# 04.net
KiCad netlist of a schematic drawn in EasyEDA
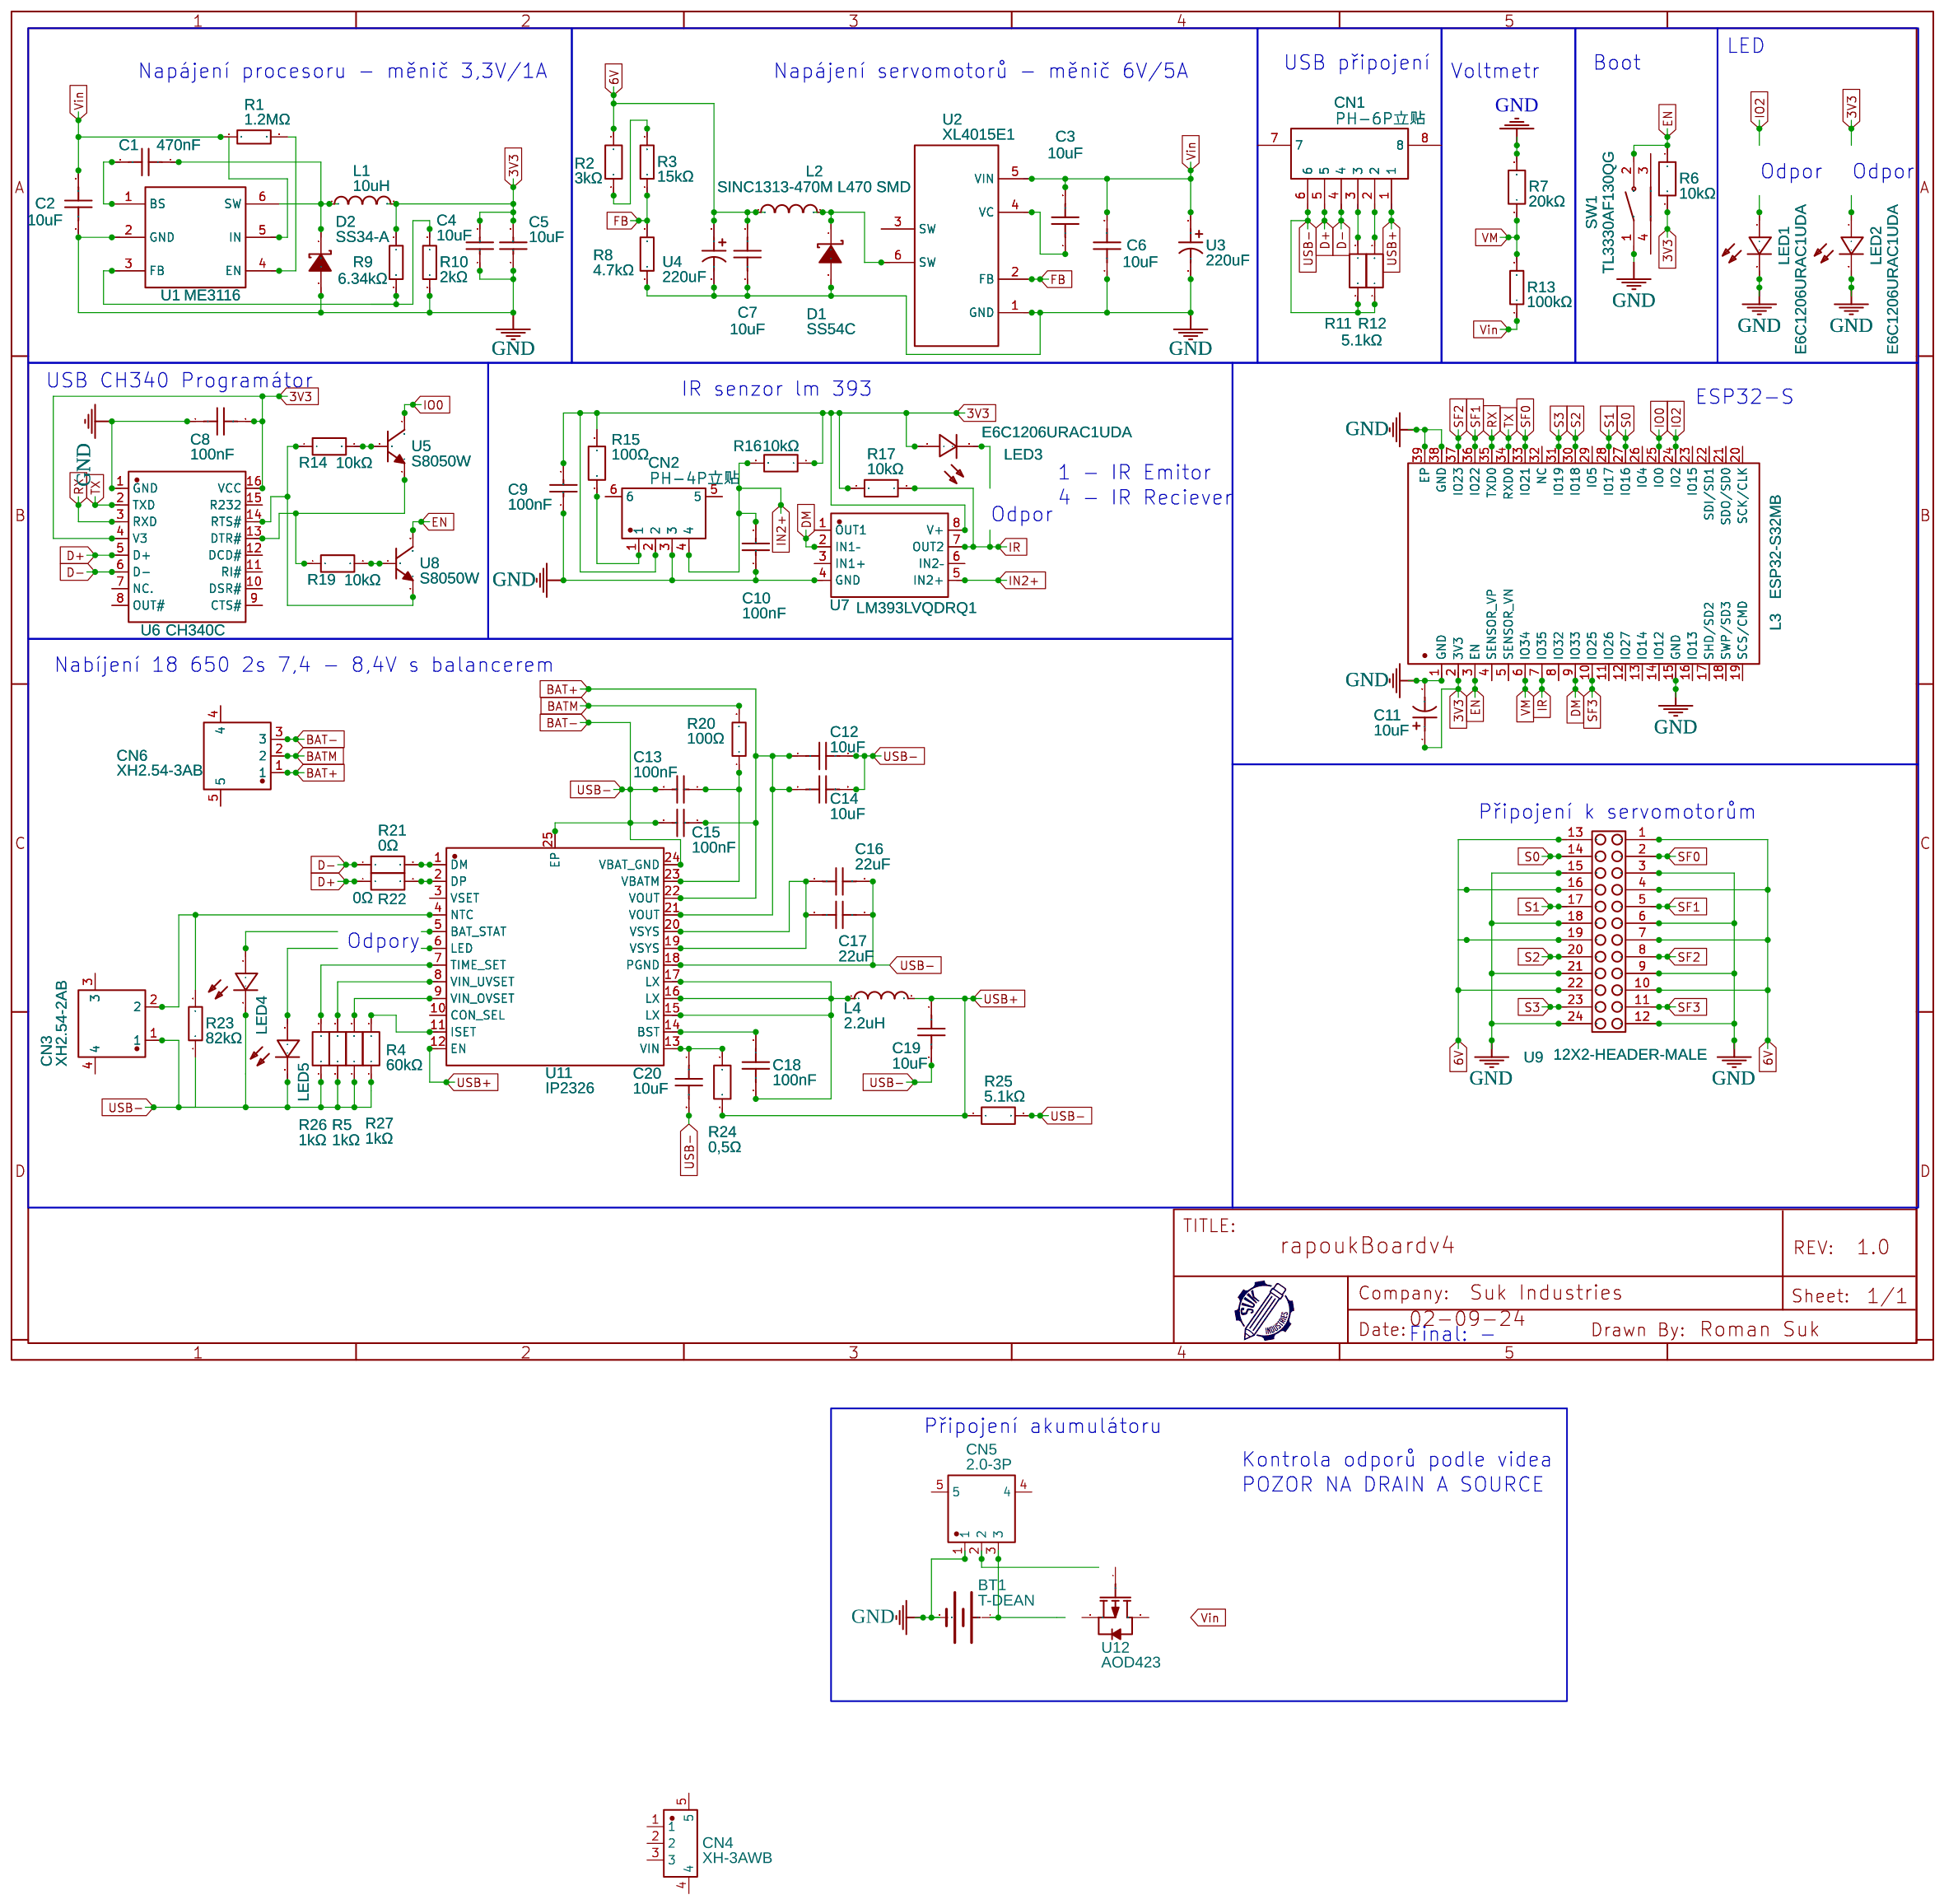
[diagram p0: schematic sheet]

(export (version "E")
  (design (tool "Eeschema 10.0.6"))
  (components
    (comp (ref "BT1") (value "T-DEAN") (libsource (lib "") (part "T-DEAN")))
    (comp (ref "C1")
      (value "470nF")
      (fields
        (field (name "Manufacturer Part") "TCC1206X7R474K500FT")
        (field (name "Manufacturer") "CCTC(三环)")
      )
      (libsource (lib "") (part "TCC1206X7R474K500FT"))
    )
    (comp (ref "C2")
      (value "10uF")
      (fields
        (field (name "Manufacturer Part") "TCC1206X7R106K250HT")
        (field (name "Manufacturer") "CCTC(三环)")
      )
      (libsource (lib "") (part "TCC1206X7R106K250HT"))
    )
    (comp (ref "C3")
      (value "10uF")
      (fields
        (field (name "Manufacturer Part") "TCC1206X7R106K250HT")
        (field (name "Manufacturer") "CCTC(三环)")
      )
      (libsource (lib "") (part "TCC1206X7R106K250HT"))
    )
    (comp (ref "C4")
      (value "10uF")
      (fields
        (field (name "Manufacturer Part") "TMK316B7106KL-TD")
        (field (name "Manufacturer") "TAIYO YUDEN(太诱)")
      )
      (libsource (lib "") (part "TMK316B7106KL-TD"))
    )
    (comp (ref "C5")
      (value "10uF")
      (fields
        (field (name "Manufacturer Part") "TMK316B7106KL-TD")
        (field (name "Manufacturer") "TAIYO YUDEN(太诱)")
      )
      (libsource (lib "") (part "TMK316B7106KL-TD"))
    )
    (comp (ref "C6")
      (value "10uF")
      (fields
        (field (name "Manufacturer Part") "TCC1206X7R106K250HT")
        (field (name "Manufacturer") "CCTC(三环)")
      )
      (libsource (lib "") (part "TCC1206X7R106K250HT"))
    )
    (comp (ref "C7")
      (value "10uF")
      (fields
        (field (name "Manufacturer Part") "TCC1206X7R106K250HT")
        (field (name "Manufacturer") "CCTC(三环)")
      )
      (libsource (lib "") (part "TCC1206X7R106K250HT"))
    )
    (comp (ref "C8")
      (value "100nF")
      (fields
        (field (name "Manufacturer Part") "1206Y1000104KXR")
        (field (name "Manufacturer") "Knowles(楼氏)")
      )
      (libsource (lib "") (part "1206Y1000104KXR"))
    )
    (comp (ref "C9")
      (value "100nF")
      (fields (field (name "Manufacturer Part") "C1206X104K451T") (field (name "Manufacturer") "IHHEC(禾伸堂)"))
      (libsource (lib "") (part "C1206X104K451T"))
    )
    (comp (ref "C10")
      (value "100nF")
      (fields (field (name "Manufacturer Part") "C1206X104K451T") (field (name "Manufacturer") "IHHEC(禾伸堂)"))
      (libsource (lib "") (part "C1206X104K451T"))
    )
    (comp (ref "C11")
      (value "10uF")
      (fields (field (name "Manufacturer Part") "RST10UF16V013") (field (name "Manufacturer") "KNSCHA(科尼盛)"))
      (libsource (lib "") (part "RST10UF16V013"))
    )
    (comp (ref "C12")
      (value "10uF")
      (fields
        (field (name "Manufacturer Part") "TCC1206X7R106K250HT")
        (field (name "Manufacturer") "CCTC(三环)")
      )
      (libsource (lib "") (part "TCC1206X7R106K250HT_1"))
    )
    (comp (ref "C13")
      (value "100nF")
      (fields (field (name "Manufacturer Part") "C1206X104K451T") (field (name "Manufacturer") "IHHEC(禾伸堂)"))
      (libsource (lib "") (part "C1206X104K451T_1"))
    )
    (comp (ref "C14")
      (value "10uF")
      (fields
        (field (name "Manufacturer Part") "TCC1206X7R106K250HT")
        (field (name "Manufacturer") "CCTC(三环)")
      )
      (libsource (lib "") (part "TCC1206X7R106K250HT_1"))
    )
    (comp (ref "C15")
      (value "100nF")
      (fields (field (name "Manufacturer Part") "C1206X104K451T") (field (name "Manufacturer") "IHHEC(禾伸堂)"))
      (libsource (lib "") (part "C1206X104K451T_1"))
    )
    (comp (ref "C16")
      (value "22uF")
      (fields
        (field (name "Manufacturer Part") "CL31X226KQHNNNE")
        (field (name "Manufacturer") "SAMSUNG(三星)")
      )
      (libsource (lib "") (part "CL31X226KQHNNNE"))
    )
    (comp (ref "C17")
      (value "22uF")
      (fields
        (field (name "Manufacturer Part") "CL31X226KQHNNNE")
        (field (name "Manufacturer") "SAMSUNG(三星)")
      )
      (libsource (lib "") (part "CL31X226KQHNNNE"))
    )
    (comp (ref "C18")
      (value "100nF")
      (fields
        (field (name "Manufacturer Part") "C1206X104J1RECAUTO7210")
        (field (name "Manufacturer") "KEMET(基美)")
      )
      (libsource (lib "") (part "C1206X104J1RECAUTO7210"))
    )
    (comp (ref "C19")
      (value "10uF")
      (fields
        (field (name "Manufacturer Part") "TCC1206X7R106K250HT")
        (field (name "Manufacturer") "CCTC(三环)")
      )
      (libsource (lib "") (part "TCC1206X7R106K250HT_2"))
    )
    (comp (ref "C20")
      (value "10uF")
      (fields
        (field (name "Manufacturer Part") "TCC1206X7R106K250HT")
        (field (name "Manufacturer") "CCTC(三环)")
      )
      (libsource (lib "") (part "TCC1206X7R106K250HT_2"))
    )
    (comp (ref "CN1")
      (value "PH-6P立贴")
      (fields (field (name "Manufacturer") "BOOMELE(博穆精密)"))
      (libsource (lib "") (part "PH-6P立贴"))
    )
    (comp (ref "CN2")
      (value "PH-4P立贴")
      (fields (field (name "Manufacturer") "BOOMELE(博穆精密)"))
      (libsource (lib "") (part "PH-4P立贴"))
    )
    (comp (ref "CN3")
      (value "XH2.54-2AB")
      (fields (field (name "Manufacturer Part") "XH-2P立贴") (field (name "Manufacturer") "BOOMELE(博穆精密)"))
      (libsource (lib "") (part "XH2.54-2AB"))
    )
    (comp (ref "CN4")
      (value "XH-3AWB")
      (fields (field (name "Manufacturer Part") "XH-3P卧贴") (field (name "Manufacturer") "BOOMELE(博穆精密)"))
      (libsource (lib "") (part "XH-3AWB"))
    )
    (comp (ref "CN5")
      (value "2.0-3P")
      (fields (field (name "Manufacturer Part") "PH-3P立贴") (field (name "Manufacturer") "BOOMELE(博穆精密)"))
      (libsource (lib "") (part "2.0-3P"))
    )
    (comp (ref "CN6")
      (value "XH2.54-3AB")
      (fields (field (name "Manufacturer Part") "XH-3P立贴") (field (name "Manufacturer") "BOOMELE(博穆精密)"))
      (libsource (lib "") (part "XH2.54-3AB"))
    )
    (comp (ref "D1")
      (value "SS54C")
      (fields (field (name "Manufacturer Part") "SS54") (field (name "Manufacturer") "LGE(鲁光)"))
      (libsource (lib "") (part "SS54C"))
    )
    (comp (ref "D2")
      (value "SS34-A")
      (fields (field (name "Manufacturer") "FMS(美丽微)"))
      (libsource (lib "") (part "SS34-A"))
    )
    (comp (ref "L1")
      (value "10uH")
      (fields
        (field (name "Manufacturer Part") "CD54YP0504-100M")
        (field (name "Manufacturer") "YJYCOIN(益嘉源)")
      )
      (libsource (lib "") (part "CD54YP0504-100M"))
    )
    (comp (ref "L2") (value "SINC1313-470M L470 SMD") (libsource (lib "") (part "SINC1313-470M L470 SMD")))
    (comp (ref "L3")
      (value "ESP32-S32MB")
      (fields
        (field (name "Manufacturer Part") "ESP32-S32Mb")
        (field (name "Manufacturer") "Ai-Thinker(安信可)")
      )
      (libsource (lib "") (part "ESP32-S32MB"))
    )
    (comp (ref "L4")
      (value "2.2uH")
      (fields (field (name "Manufacturer Part") "CD54-2R2M-T") (field (name "Manufacturer") "Me-TECH(美台高科)"))
      (libsource (lib "") (part "CD54-2R2M-T"))
    )
    (comp (ref "LED1")
      (value "E6C1206URAC1UDA")
      (fields (field (name "Manufacturer") "ekinglux(亿晶源)"))
      (libsource (lib "") (part "E6C1206URAC1UDA"))
    )
    (comp (ref "LED2")
      (value "E6C1206URAC1UDA")
      (fields (field (name "Manufacturer") "ekinglux(亿晶源)"))
      (libsource (lib "") (part "E6C1206URAC1UDA"))
    )
    (comp (ref "LED3")
      (value "E6C1206URAC1UDA")
      (fields (field (name "Manufacturer") "ekinglux(亿晶源)"))
      (libsource (lib "") (part "E6C1206URAC1UDA_1"))
    )
    (comp (ref "LED4")
      (value "E6C1206URAC1UDA")
      (fields (field (name "Manufacturer") "ekinglux(亿晶源)"))
      (libsource (lib "") (part "E6C1206URAC1UDA"))
    )
    (comp (ref "LED5")
      (value "E6C1206URAC1UDA")
      (fields (field (name "Manufacturer") "ekinglux(亿晶源)"))
      (libsource (lib "") (part "E6C1206URAC1UDA"))
    )
    (comp (ref "R1")
      (value "1.2MΩ")
      (fields (field (name "Manufacturer Part") "RMC06031.2M1%N") (field (name "Manufacturer") "Tyohm(幸亚电阻)"))
      (libsource (lib "") (part "RMC06031.2M1%N"))
    )
    (comp (ref "R2")
      (value "3kΩ")
      (fields
        (field (name "Manufacturer Part") "CR1206J3K00P05Z")
        (field (name "Manufacturer") "EVER OHMS(天二科技)")
      )
      (libsource (lib "") (part "CR1206J3K00P05Z"))
    )
    (comp (ref "R3")
      (value "15kΩ")
      (fields (field (name "Manufacturer Part") "RT1206FRD0715KL") (field (name "Manufacturer") "YAGEO(国巨)"))
      (libsource (lib "") (part "RT1206FRD0715KL"))
    )
    (comp (ref "R4")
      (value "60kΩ")
      (fields
        (field (name "Manufacturer Part") "MCA12060D6002BP500")
        (field (name "Manufacturer") "VISHAY(威世)")
      )
      (libsource (lib "") (part "MCA12060D6002BP500"))
    )
    (comp (ref "R5")
      (value "1kΩ")
      (fields (field (name "Manufacturer Part") "SCR1206J1K") (field (name "Manufacturer") "VO(翔胜)"))
      (libsource (lib "") (part "SCR1206J1K"))
    )
    (comp (ref "R6")
      (value "10kΩ")
      (fields (field (name "Manufacturer Part") "SCR1206F10K") (field (name "Manufacturer") "VO(翔胜)"))
      (libsource (lib "") (part "SCR1206F10K_2"))
    )
    (comp (ref "R7")
      (value "20kΩ")
      (fields
        (field (name "Manufacturer Part") "CR1206F20KP05")
        (field (name "Manufacturer") "EVER OHMS(天二科技)")
      )
      (libsource (lib "") (part "CR1206F20KP05"))
    )
    (comp (ref "R8")
      (value "4.7kΩ")
      (fields
        (field (name "Manufacturer Part") "CRCW12064K70FKEA")
        (field (name "Manufacturer") "VISHAY(威世)")
      )
      (libsource (lib "") (part "CRCW12064K70FKEA"))
    )
    (comp (ref "R9")
      (value "6.34kΩ")
      (fields (field (name "Manufacturer Part") "RS-06K6341FT") (field (name "Manufacturer") "FH(风华)"))
      (libsource (lib "") (part "RS-06K6341FT"))
    )
    (comp (ref "R10")
      (value "2kΩ")
      (fields (field (name "Manufacturer Part") "RTT06202JTP") (field (name "Manufacturer") "RALEC(旺诠)"))
      (libsource (lib "") (part "RTT06202JTP"))
    )
    (comp (ref "R11")
      (value "5.1kΩ")
      (fields
        (field (name "Manufacturer Part") "HoARG0603-1/10W-5.1KR-0.1%-TCR25")
        (field (name "Manufacturer") "Milliohm(毫欧)")
      )
      (libsource (lib "") (part "HOARG0603-1/10W-5.1KR-0.1%-TCR25_1"))
    )
    (comp (ref "R12")
      (value "5.1kΩ")
      (fields
        (field (name "Manufacturer Part") "HoARG0603-1/10W-5.1KR-0.1%-TCR25")
        (field (name "Manufacturer") "Milliohm(毫欧)")
      )
      (libsource (lib "") (part "HOARG0603-1/10W-5.1KR-0.1%-TCR25_1"))
    )
    (comp (ref "R13")
      (value "100kΩ")
      (fields
        (field (name "Manufacturer Part") "QR1206F100KP05Z")
        (field (name "Manufacturer") "EVER OHMS(天二科技)")
      )
      (libsource (lib "") (part "QR1206F100KP05"))
    )
    (comp (ref "R14")
      (value "10kΩ")
      (fields (field (name "Manufacturer Part") "SCR1206F10K") (field (name "Manufacturer") "VO(翔胜)"))
      (libsource (lib "") (part "SCR1206F10K"))
    )
    (comp (ref "R15")
      (value "100Ω")
      (fields (field (name "Manufacturer Part") "SCR1206F100R") (field (name "Manufacturer") "VO(翔胜)"))
      (libsource (lib "") (part "SCR1206F100R"))
    )
    (comp (ref "R16")
      (value "10kΩ")
      (fields (field (name "Manufacturer Part") "SCR1206F10K") (field (name "Manufacturer") "VO(翔胜)"))
      (libsource (lib "") (part "SCR1206F10K_1"))
    )
    (comp (ref "R17")
      (value "10kΩ")
      (fields (field (name "Manufacturer Part") "SCR1206F10K") (field (name "Manufacturer") "VO(翔胜)"))
      (libsource (lib "") (part "SCR1206F10K"))
    )
    (comp (ref "R19")
      (value "10kΩ")
      (fields (field (name "Manufacturer Part") "SCR1206F10K") (field (name "Manufacturer") "VO(翔胜)"))
      (libsource (lib "") (part "SCR1206F10K"))
    )
    (comp (ref "R20")
      (value "100Ω")
      (fields (field (name "Manufacturer Part") "AECR1206F100RK9") (field (name "Manufacturer") "RESI(开步睿思)"))
      (libsource (lib "") (part "AECR1206F100RK9"))
    )
    (comp (ref "R21")
      (value "0Ω")
      (fields
        (field (name "Manufacturer Part") "CR1206J0R00P05Z")
        (field (name "Manufacturer") "EVER OHMS(天二科技)")
      )
      (libsource (lib "") (part "CR1206J0R00P05Z"))
    )
    (comp (ref "R22")
      (value "0Ω")
      (fields
        (field (name "Manufacturer Part") "CR1206J0R00P05Z")
        (field (name "Manufacturer") "EVER OHMS(天二科技)")
      )
      (libsource (lib "") (part "CR1206J0R00P05Z"))
    )
    (comp (ref "R23")
      (value "82kΩ")
      (fields (field (name "Manufacturer Part") "AECR1206F82K0K9") (field (name "Manufacturer") "RESI(开步睿思)"))
      (libsource (lib "") (part "AECR1206F82K0K9"))
    )
    (comp (ref "R24")
      (value "0,5Ω")
      (fields (field (name "Manufacturer Part") "SCR1206F10K") (field (name "Manufacturer") "VO(翔胜)"))
      (libsource (lib "") (part "SCR1206F10K_2"))
    )
    (comp (ref "R25")
      (value "5.1kΩ")
      (fields
        (field (name "Manufacturer Part") "HoARG0603-1/10W-5.1KR-0.1%-TCR25")
        (field (name "Manufacturer") "Milliohm(毫欧)")
      )
      (libsource (lib "") (part "HOARG0603-1/10W-5.1KR-0.1%-TCR25"))
    )
    (comp (ref "R26")
      (value "1kΩ")
      (fields (field (name "Manufacturer Part") "SCR1206J1K") (field (name "Manufacturer") "VO(翔胜)"))
      (libsource (lib "") (part "SCR1206J1K"))
    )
    (comp (ref "R27")
      (value "1kΩ")
      (fields (field (name "Manufacturer Part") "SCR1206J1K") (field (name "Manufacturer") "VO(翔胜)"))
      (libsource (lib "") (part "SCR1206J1K"))
    )
    (comp (ref "SW1")
      (value "TL3330AF130QG")
      (fields (field (name "Manufacturer") "E-Switch"))
      (libsource (lib "") (part "TL3330AF130QG"))
    )
    (comp (ref "U1")
      (value "ME3116")
      (fields (field (name "Manufacturer Part") "ME3116AM6G") (field (name "Manufacturer") "MICRONE(南京微盟)"))
      (libsource (lib "") (part "ME3116"))
    )
    (comp (ref "U2")
      (value "XL4015E1")
      (fields (field (name "Manufacturer") "XLSEMI(芯龙)"))
      (libsource (lib "") (part "XL4015E1"))
    )
    (comp (ref "U3")
      (value "220uF")
      (fields
        (field (name "Manufacturer Part") "CK220UF16V167RV0142")
        (field (name "Manufacturer") "KNSCHA(科尼盛)")
      )
      (libsource (lib "") (part "CK220UF16V167RV0142"))
    )
    (comp (ref "U4")
      (value "220uF")
      (fields
        (field (name "Manufacturer Part") "CK220UF16V167RV0142")
        (field (name "Manufacturer") "KNSCHA(科尼盛)")
      )
      (libsource (lib "") (part "CK220UF16V167RV0142"))
    )
    (comp (ref "U5")
      (value "S8050W")
      (fields (field (name "Manufacturer") "Slkor(萨科微)"))
      (libsource (lib "") (part "S8050W"))
    )
    (comp (ref "U6")
      (value "CH340C")
      (fields (field (name "Manufacturer") "WCH(南京沁恒)"))
      (libsource (lib "") (part "CH340C"))
    )
    (comp (ref "U7")
      (value "LM393LVQDRQ1")
      (fields (field (name "Manufacturer") "TI(德州仪器)"))
      (libsource (lib "") (part "LM393LVQDRQ1"))
    )
    (comp (ref "U8")
      (value "S8050W")
      (fields (field (name "Manufacturer") "Slkor(萨科微)"))
      (libsource (lib "") (part "S8050W"))
    )
    (comp (ref "U9") (value "12X2-HEADER-MALE") (libsource (lib "") (part "12X2-HEADER-MALE")))
    (comp (ref "U11")
      (value "IP2326")
      (fields (field (name "Manufacturer") "INJOINIC(英集芯)"))
      (libsource (lib "") (part "IP2326"))
    )
    (comp (ref "U12")
      (value "AOD423")
      (fields (field (name "Manufacturer") "AOS"))
      (libsource (lib "") (part "AOD423"))
    )
  )
  (nets
    (net (code "1") (name "3V3") (class "Default")
      (node (ref "C11") (pin "1") (pinfunction "1_1") (pintype "input"))
      (node (ref "C4") (pin "2") (pinfunction "2_2") (pintype "input"))
      (node (ref "C5") (pin "2") (pinfunction "2_2") (pintype "input"))
      (node (ref "C8") (pin "2") (pinfunction "2_2") (pintype "unspecified"))
      (node (ref "C9") (pin "2") (pinfunction "2_2") (pintype "input"))
      (node (ref "CN2") (pin "2") (pinfunction "2_2") (pintype "unspecified"))
      (node (ref "L1") (pin "2") (pinfunction "2_2") (pintype "unspecified"))
      (node (ref "L3") (pin "2") (pinfunction "3V3_2") (pintype "unspecified"))
      (node (ref "LED3") (pin "1") (pinfunction "+_1") (pintype "unspecified"))
      (node (ref "R15") (pin "1") (pinfunction "1_1") (pintype "unspecified"))
      (node (ref "R16") (pin "1") (pinfunction "1_1") (pintype "unspecified"))
      (node (ref "R17") (pin "1") (pinfunction "1_1") (pintype "unspecified"))
      (node (ref "R6") (pin "2") (pinfunction "2_2") (pintype "unspecified"))
      (node (ref "R9") (pin "1") (pinfunction "1_1") (pintype "unspecified"))
      (node (ref "U6") (pin "16") (pinfunction "VCC_16") (pintype "unspecified"))
      (node (ref "U6") (pin "4") (pinfunction "V3_4") (pintype "unspecified"))
      (node (ref "U7") (pin "8") (pinfunction "V+_8") (pintype "unspecified"))
    )
    (net (code "2") (name "6V") (class "Default")
      (node (ref "C7") (pin "2") (pinfunction "2_2") (pintype "unspecified"))
      (node (ref "L2") (pin "1") (pinfunction "1_1") (pintype "unspecified"))
      (node (ref "R2") (pin "2") (pinfunction "2_2") (pintype "unspecified"))
      (node (ref "U4") (pin "1") (pinfunction "1_1") (pintype "input"))
      (node (ref "U9") (pin "1") (pinfunction "1_1") (pintype "unspecified"))
      (node (ref "U9") (pin "10") (pinfunction "10_10") (pintype "unspecified"))
      (node (ref "U9") (pin "13") (pinfunction "13_13") (pintype "unspecified"))
      (node (ref "U9") (pin "16") (pinfunction "16_16") (pintype "unspecified"))
      (node (ref "U9") (pin "19") (pinfunction "19_19") (pintype "unspecified"))
      (node (ref "U9") (pin "22") (pinfunction "22_22") (pintype "unspecified"))
      (node (ref "U9") (pin "4") (pinfunction "4_4") (pintype "unspecified"))
      (node (ref "U9") (pin "7") (pinfunction "7_7") (pintype "unspecified"))
    )
    (net (code "3") (name "BAT+") (class "Default")
      (node (ref "C12") (pin "1") (pinfunction "1_1") (pintype "unspecified"))
      (node (ref "C14") (pin "1") (pinfunction "1_1") (pintype "unspecified"))
      (node (ref "C15") (pin "1") (pinfunction "1_1") (pintype "input"))
      (node (ref "CN6") (pin "1") (pinfunction "1_1") (pintype "unspecified"))
      (node (ref "U11") (pin "21") (pinfunction "VOUT_21") (pintype "unspecified"))
      (node (ref "U11") (pin "22") (pinfunction "VOUT_22") (pintype "unspecified"))
    )
    (net (code "4") (name "BAT-") (class "Default")
      (node (ref "C12") (pin "2") (pinfunction "2_2") (pintype "unspecified"))
      (node (ref "C13") (pin "2") (pinfunction "2_2") (pintype "input"))
      (node (ref "C14") (pin "2") (pinfunction "2_2") (pintype "unspecified"))
      (node (ref "C15") (pin "2") (pinfunction "2_2") (pintype "input"))
      (node (ref "C16") (pin "2") (pinfunction "2_2") (pintype "unspecified"))
      (node (ref "C17") (pin "2") (pinfunction "2_2") (pintype "unspecified"))
      (node (ref "C19") (pin "2") (pinfunction "2_2") (pintype "unspecified"))
      (node (ref "C20") (pin "2") (pinfunction "2_2") (pintype "unspecified"))
      (node (ref "CN1") (pin "6") (pinfunction "6_6") (pintype "unspecified"))
      (node (ref "CN3") (pin "1") (pinfunction "1_1") (pintype "unspecified"))
      (node (ref "CN6") (pin "3") (pinfunction "3_3") (pintype "unspecified"))
      (node (ref "LED4") (pin "2") (pinfunction "-_2") (pintype "unspecified"))
      (node (ref "LED5") (pin "2") (pinfunction "-_2") (pintype "unspecified"))
      (node (ref "R11") (pin "1") (pinfunction "1_1") (pintype "unspecified"))
      (node (ref "R12") (pin "1") (pinfunction "1_1") (pintype "unspecified"))
      (node (ref "R23") (pin "1") (pinfunction "1_1") (pintype "unspecified"))
      (node (ref "R25") (pin "2") (pinfunction "2_2") (pintype "unspecified"))
      (node (ref "R26") (pin "1") (pinfunction "1_1") (pintype "unspecified"))
      (node (ref "R27") (pin "1") (pinfunction "1_1") (pintype "unspecified"))
      (node (ref "R4") (pin "1") (pinfunction "1_1") (pintype "unspecified"))
      (node (ref "R5") (pin "1") (pinfunction "1_1") (pintype "unspecified"))
      (node (ref "U11") (pin "18") (pinfunction "PGND_18") (pintype "unspecified"))
      (node (ref "U11") (pin "24") (pinfunction "VBAT_GND_24") (pintype "unspecified"))
      (node (ref "U11") (pin "25") (pinfunction "EP_25") (pintype "unspecified"))
    )
    (net (code "5") (name "BATM") (class "Default")
      (node (ref "CN6") (pin "2") (pinfunction "2_2") (pintype "unspecified"))
      (node (ref "R20") (pin "2") (pinfunction "2_2") (pintype "unspecified"))
    )
    (net (code "6") (name "D+") (class "Default")
      (node (ref "CN1") (pin "5") (pinfunction "5_5") (pintype "unspecified"))
      (node (ref "R22") (pin "1") (pinfunction "1_1") (pintype "unspecified"))
      (node (ref "U6") (pin "5") (pinfunction "D+_5") (pintype "unspecified"))
    )
    (net (code "7") (name "D-") (class "Default")
      (node (ref "CN1") (pin "4") (pinfunction "4_4") (pintype "unspecified"))
      (node (ref "R21") (pin "1") (pinfunction "1_1") (pintype "unspecified"))
      (node (ref "U6") (pin "6") (pinfunction "D-_6") (pintype "unspecified"))
    )
    (net (code "8") (name "DM") (class "Default")
      (node (ref "L3") (pin "9") (pinfunction "IO33_9") (pintype "unspecified"))
      (node (ref "U7") (pin "2") (pinfunction "IN1–_2") (pintype "unspecified"))
    )
    (net (code "9") (name "EN") (class "Default")
      (node (ref "L3") (pin "3") (pinfunction "EN_3") (pintype "unspecified"))
      (node (ref "R6") (pin "1") (pinfunction "1_1") (pintype "unspecified"))
      (node (ref "SW1") (pin "2") (pinfunction "2_2") (pintype "unspecified"))
      (node (ref "U8") (pin "3") (pinfunction "C_3") (pintype "unspecified"))
    )
    (net (code "10") (name "FB") (class "Default")
      (node (ref "R3") (pin "1") (pinfunction "1_1") (pintype "unspecified"))
      (node (ref "R8") (pin "2") (pinfunction "2_2") (pintype "unspecified"))
      (node (ref "U2") (pin "2") (pinfunction "FB_2") (pintype "unspecified"))
    )
    (net (code "11") (name "GND") (class "Default")
      (node (ref "BT1") (pin "2") (pinfunction "2_2") (pintype "bidirectional"))
      (node (ref "C10") (pin "1") (pinfunction "1_1") (pintype "input"))
      (node (ref "C11") (pin "2") (pinfunction "2_2") (pintype "input"))
      (node (ref "C2") (pin "1") (pinfunction "1_1") (pintype "unspecified"))
      (node (ref "C4") (pin "1") (pinfunction "1_1") (pintype "input"))
      (node (ref "C5") (pin "1") (pinfunction "1_1") (pintype "input"))
      (node (ref "C6") (pin "1") (pinfunction "1_1") (pintype "unspecified"))
      (node (ref "C7") (pin "1") (pinfunction "1_1") (pintype "unspecified"))
      (node (ref "C8") (pin "1") (pinfunction "1_1") (pintype "unspecified"))
      (node (ref "C9") (pin "1") (pinfunction "1_1") (pintype "input"))
      (node (ref "CN2") (pin "3") (pinfunction "3_3") (pintype "unspecified"))
      (node (ref "CN5") (pin "1") (pinfunction "1_1") (pintype "unspecified"))
      (node (ref "D1") (pin "2") (pinfunction "A_2") (pintype "unspecified"))
      (node (ref "D2") (pin "2") (pinfunction "A_2") (pintype "unspecified"))
      (node (ref "L3") (pin "1") (pinfunction "GND_1") (pintype "unspecified"))
      (node (ref "L3") (pin "15") (pinfunction "GND_15") (pintype "unspecified"))
      (node (ref "L3") (pin "38") (pinfunction "GND_38") (pintype "unspecified"))
      (node (ref "L3") (pin "39") (pinfunction "EP_39") (pintype "unspecified"))
      (node (ref "LED1") (pin "2") (pinfunction "-_2") (pintype "unspecified"))
      (node (ref "LED2") (pin "2") (pinfunction "-_2") (pintype "unspecified"))
      (node (ref "R10") (pin "1") (pinfunction "1_1") (pintype "input"))
      (node (ref "R7") (pin "2") (pinfunction "2_2") (pintype "unspecified"))
      (node (ref "R8") (pin "1") (pinfunction "1_1") (pintype "unspecified"))
      (node (ref "SW1") (pin "1") (pinfunction "1_1") (pintype "unspecified"))
      (node (ref "U1") (pin "2") (pinfunction "GND_2") (pintype "unspecified"))
      (node (ref "U2") (pin "1") (pinfunction "GND_1") (pintype "unspecified"))
      (node (ref "U3") (pin "2") (pinfunction "2_2") (pintype "input"))
      (node (ref "U4") (pin "2") (pinfunction "2_2") (pintype "input"))
      (node (ref "U6") (pin "1") (pinfunction "GND_1") (pintype "unspecified"))
      (node (ref "U7") (pin "4") (pinfunction "GND_4") (pintype "unspecified"))
      (node (ref "U9") (pin "12") (pinfunction "12_12") (pintype "unspecified"))
      (node (ref "U9") (pin "15") (pinfunction "15_15") (pintype "unspecified"))
      (node (ref "U9") (pin "18") (pinfunction "18_18") (pintype "unspecified"))
      (node (ref "U9") (pin "21") (pinfunction "21_21") (pintype "unspecified"))
      (node (ref "U9") (pin "24") (pinfunction "24_24") (pintype "unspecified"))
      (node (ref "U9") (pin "3") (pinfunction "3_3") (pintype "unspecified"))
      (node (ref "U9") (pin "6") (pinfunction "6_6") (pintype "unspecified"))
      (node (ref "U9") (pin "9") (pinfunction "9_9") (pintype "unspecified"))
    )
    (net (code "12") (name "IN2+") (class "Default")
      (node (ref "C10") (pin "2") (pinfunction "2_2") (pintype "input"))
      (node (ref "CN2") (pin "4") (pinfunction "4_4") (pintype "unspecified"))
      (node (ref "R16") (pin "2") (pinfunction "2_2") (pintype "unspecified"))
      (node (ref "U7") (pin "5") (pinfunction "IN2+_5") (pintype "unspecified"))
    )
    (net (code "13") (name "IO0") (class "Default")
      (node (ref "L3") (pin "25") (pinfunction "IO0_25") (pintype "unspecified"))
      (node (ref "U5") (pin "3") (pinfunction "C_3") (pintype "unspecified"))
    )
    (net (code "14") (name "IO2") (class "Default")
      (node (ref "L3") (pin "24") (pinfunction "IO2_24") (pintype "unspecified"))
    )
    (net (code "15") (name "IR") (class "Default")
      (node (ref "L3") (pin "7") (pinfunction "IO35_7") (pintype "unspecified"))
      (node (ref "R17") (pin "2") (pinfunction "2_2") (pintype "unspecified"))
      (node (ref "U7") (pin "7") (pinfunction "OUT2_7") (pintype "unspecified"))
    )
    (net (code "16") (name "Net-(BT1-Pad1)") (class "Default")
      (node (ref "BT1") (pin "1") (pinfunction "1_1") (pintype "bidirectional"))
      (node (ref "CN5") (pin "3") (pinfunction "3_3") (pintype "unspecified"))
    )
    (net (code "17") (name "Net-(C16-Pad1)") (class "Default")
      (node (ref "C16") (pin "1") (pinfunction "1_1") (pintype "unspecified"))
      (node (ref "C17") (pin "1") (pinfunction "1_1") (pintype "unspecified"))
      (node (ref "U11") (pin "19") (pinfunction "VSYS_19") (pintype "unspecified"))
      (node (ref "U11") (pin "20") (pinfunction "VSYS_20") (pintype "unspecified"))
    )
    (net (code "18") (name "Net-(C18-Pad1)") (class "Default")
      (node (ref "C18") (pin "1") (pinfunction "1_1") (pintype "unspecified"))
      (node (ref "L4") (pin "1") (pinfunction "1_1") (pintype "unspecified"))
      (node (ref "U11") (pin "15") (pinfunction "LX_15") (pintype "unspecified"))
      (node (ref "U11") (pin "16") (pinfunction "LX_16") (pintype "unspecified"))
      (node (ref "U11") (pin "17") (pinfunction "LX_17") (pintype "unspecified"))
    )
    (net (code "19") (name "Net-(CN1-Pad2)") (class "Default")
      (node (ref "CN1") (pin "2") (pinfunction "2_2") (pintype "unspecified"))
      (node (ref "R12") (pin "2") (pinfunction "2_2") (pintype "unspecified"))
    )
    (net (code "20") (name "Net-(CN1-Pad3)") (class "Default")
      (node (ref "CN1") (pin "3") (pinfunction "3_3") (pintype "unspecified"))
      (node (ref "R11") (pin "2") (pinfunction "2_2") (pintype "unspecified"))
    )
    (net (code "21") (name "Net-(CN2-Pad1)") (class "Default")
      (node (ref "CN2") (pin "1") (pinfunction "1_1") (pintype "unspecified"))
      (node (ref "R15") (pin "2") (pinfunction "2_2") (pintype "unspecified"))
    )
    (net (code "22") (name "Net-(D1-K)") (class "Default")
      (node (ref "D1") (pin "1") (pinfunction "K_1") (pintype "unspecified"))
      (node (ref "L2") (pin "2") (pinfunction "2_2") (pintype "unspecified"))
      (node (ref "U2") (pin "6") (pinfunction "SW_6") (pintype "unspecified"))
    )
    (net (code "23") (name "Net-(D2-C)") (class "Default")
      (node (ref "C1") (pin "1") (pinfunction "1_1") (pintype "unspecified"))
      (node (ref "D2") (pin "1") (pinfunction "C_1") (pintype "unspecified"))
      (node (ref "L1") (pin "1") (pinfunction "1_1") (pintype "unspecified"))
      (node (ref "U1") (pin "6") (pinfunction "SW_6") (pintype "unspecified"))
    )
    (net (code "24") (name "Net-(R2-Pad1)") (class "Default")
      (node (ref "R2") (pin "1") (pinfunction "1_1") (pintype "unspecified"))
      (node (ref "R3") (pin "2") (pinfunction "2_2") (pintype "unspecified"))
    )
    (net (code "25") (name "Net-(U1-BS)") (class "Default")
      (node (ref "C1") (pin "2") (pinfunction "2_2") (pintype "unspecified"))
      (node (ref "U1") (pin "1") (pinfunction "BS_1") (pintype "unspecified"))
    )
    (net (code "26") (name "Net-(U1-EN)") (class "Default")
      (node (ref "R1") (pin "2") (pinfunction "2_2") (pintype "unspecified"))
      (node (ref "U1") (pin "4") (pinfunction "EN_4") (pintype "unspecified"))
    )
    (net (code "27") (name "Net-(U1-FB)") (class "Default")
      (node (ref "R10") (pin "2") (pinfunction "2_2") (pintype "input"))
      (node (ref "R9") (pin "2") (pinfunction "2_2") (pintype "unspecified"))
      (node (ref "U1") (pin "3") (pinfunction "FB_3") (pintype "unspecified"))
    )
    (net (code "28") (name "Net-(U2-VC)") (class "Default")
      (node (ref "C3") (pin "1") (pinfunction "1_1") (pintype "unspecified"))
      (node (ref "U2") (pin "4") (pinfunction "VC_4") (pintype "unspecified"))
    )
    (net (code "29") (name "Net-(U5-B)") (class "Default")
      (node (ref "R14") (pin "2") (pinfunction "2_2") (pintype "unspecified"))
      (node (ref "U5") (pin "1") (pinfunction "B_1") (pintype "unspecified"))
    )
    (net (code "30") (name "Net-(U5-E)") (class "Default")
      (node (ref "R19") (pin "1") (pinfunction "1_1") (pintype "unspecified"))
      (node (ref "U5") (pin "2") (pinfunction "E_2") (pintype "unspecified"))
      (node (ref "U6") (pin "13") (pinfunction "DTR#_13") (pintype "unspecified"))
    )
    (net (code "31") (name "Net-(U6-RTS#)") (class "Default")
      (node (ref "R14") (pin "1") (pinfunction "1_1") (pintype "unspecified"))
      (node (ref "U6") (pin "14") (pinfunction "RTS#_14") (pintype "unspecified"))
      (node (ref "U8") (pin "2") (pinfunction "E_2") (pintype "unspecified"))
    )
    (net (code "32") (name "Net-(U8-B)") (class "Default")
      (node (ref "R19") (pin "2") (pinfunction "2_2") (pintype "unspecified"))
      (node (ref "U8") (pin "1") (pinfunction "B_1") (pintype "unspecified"))
    )
    (net (code "33") (name "Net-(U11-BST)") (class "Default")
      (node (ref "C18") (pin "2") (pinfunction "2_2") (pintype "unspecified"))
      (node (ref "U11") (pin "14") (pinfunction "BST_14") (pintype "unspecified"))
    )
    (net (code "34") (name "Net-(U11-DM)") (class "Default")
      (node (ref "R21") (pin "2") (pinfunction "2_2") (pintype "unspecified"))
      (node (ref "U11") (pin "1") (pinfunction "DM_1") (pintype "unspecified"))
    )
    (net (code "35") (name "Net-(U11-DP)") (class "Default")
      (node (ref "R22") (pin "2") (pinfunction "2_2") (pintype "unspecified"))
      (node (ref "U11") (pin "2") (pinfunction "DP_2") (pintype "unspecified"))
    )
    (net (code "36") (name "Net-(U11-ISET)") (class "Default")
      (node (ref "R4") (pin "2") (pinfunction "2_2") (pintype "unspecified"))
      (node (ref "U11") (pin "11") (pinfunction "ISET_11") (pintype "unspecified"))
    )
    (net (code "37") (name "Net-(U11-NTC)") (class "Default")
      (node (ref "CN3") (pin "2") (pinfunction "2_2") (pintype "unspecified"))
      (node (ref "R23") (pin "2") (pinfunction "2_2") (pintype "unspecified"))
      (node (ref "U11") (pin "4") (pinfunction "NTC_4") (pintype "unspecified"))
    )
    (net (code "38") (name "Net-(U11-TIME_SET)") (class "Default")
      (node (ref "R26") (pin "2") (pinfunction "2_2") (pintype "unspecified"))
      (node (ref "U11") (pin "7") (pinfunction "TIME_SET_7") (pintype "unspecified"))
    )
    (net (code "39") (name "Net-(U11-VBATM)") (class "Default")
      (node (ref "C13") (pin "1") (pinfunction "1_1") (pintype "input"))
      (node (ref "R20") (pin "1") (pinfunction "1_1") (pintype "unspecified"))
      (node (ref "U11") (pin "23") (pinfunction "VBATM_23") (pintype "unspecified"))
    )
    (net (code "40") (name "Net-(U11-VIN)") (class "Default")
      (node (ref "C20") (pin "1") (pinfunction "1_1") (pintype "unspecified"))
      (node (ref "R24") (pin "1") (pinfunction "1_1") (pintype "unspecified"))
      (node (ref "U11") (pin "13") (pinfunction "VIN_13") (pintype "unspecified"))
    )
    (net (code "41") (name "Net-(U11-VIN_OVSET)") (class "Default")
      (node (ref "R27") (pin "2") (pinfunction "2_2") (pintype "unspecified"))
      (node (ref "U11") (pin "9") (pinfunction "VIN_OVSET_9") (pintype "unspecified"))
    )
    (net (code "42") (name "Net-(U11-VIN_UVSET)") (class "Default")
      (node (ref "R5") (pin "2") (pinfunction "2_2") (pintype "unspecified"))
      (node (ref "U11") (pin "8") (pinfunction "VIN_UVSET_8") (pintype "unspecified"))
    )
    (net (code "43") (name "RX") (class "Default")
      (node (ref "L3") (pin "35") (pinfunction "TXD0_35") (pintype "unspecified"))
      (node (ref "U6") (pin "3") (pinfunction "RXD_3") (pintype "unspecified"))
    )
    (net (code "44") (name "S0") (class "Default")
      (node (ref "L3") (pin "27") (pinfunction "IO16_27") (pintype "unspecified"))
      (node (ref "U9") (pin "14") (pinfunction "14_14") (pintype "unspecified"))
    )
    (net (code "45") (name "S1") (class "Default")
      (node (ref "L3") (pin "28") (pinfunction "IO17_28") (pintype "unspecified"))
      (node (ref "U9") (pin "17") (pinfunction "17_17") (pintype "unspecified"))
    )
    (net (code "46") (name "S2") (class "Default")
      (node (ref "L3") (pin "30") (pinfunction "IO18_30") (pintype "unspecified"))
      (node (ref "U9") (pin "20") (pinfunction "20_20") (pintype "unspecified"))
    )
    (net (code "47") (name "S3") (class "Default")
      (node (ref "L3") (pin "31") (pinfunction "IO19_31") (pintype "unspecified"))
      (node (ref "U9") (pin "23") (pinfunction "23_23") (pintype "unspecified"))
    )
    (net (code "48") (name "SF0") (class "Default")
      (node (ref "L3") (pin "33") (pinfunction "IO21_33") (pintype "unspecified"))
      (node (ref "U9") (pin "2") (pinfunction "2_2") (pintype "unspecified"))
    )
    (net (code "49") (name "SF1") (class "Default")
      (node (ref "L3") (pin "36") (pinfunction "IO22_36") (pintype "unspecified"))
      (node (ref "U9") (pin "5") (pinfunction "5_5") (pintype "unspecified"))
    )
    (net (code "50") (name "SF2") (class "Default")
      (node (ref "L3") (pin "37") (pinfunction "IO23_37") (pintype "unspecified"))
      (node (ref "U9") (pin "8") (pinfunction "8_8") (pintype "unspecified"))
    )
    (net (code "51") (name "SF3") (class "Default")
      (node (ref "L3") (pin "10") (pinfunction "IO25_10") (pintype "unspecified"))
      (node (ref "U9") (pin "11") (pinfunction "11_11") (pintype "unspecified"))
    )
    (net (code "52") (name "TX") (class "Default")
      (node (ref "L3") (pin "34") (pinfunction "RXD0_34") (pintype "unspecified"))
      (node (ref "U6") (pin "2") (pinfunction "TXD_2") (pintype "unspecified"))
    )
    (net (code "53") (name "USB+") (class "Default")
      (node (ref "C19") (pin "1") (pinfunction "1_1") (pintype "unspecified"))
      (node (ref "CN1") (pin "1") (pinfunction "1_1") (pintype "unspecified"))
      (node (ref "L4") (pin "2") (pinfunction "2_2") (pintype "unspecified"))
      (node (ref "R24") (pin "2") (pinfunction "2_2") (pintype "unspecified"))
      (node (ref "R25") (pin "1") (pinfunction "1_1") (pintype "unspecified"))
      (node (ref "U11") (pin "12") (pinfunction "EN_12") (pintype "unspecified"))
    )
    (net (code "54") (name "VM") (class "Default")
      (node (ref "L3") (pin "6") (pinfunction "IO34_6") (pintype "unspecified"))
      (node (ref "R13") (pin "2") (pinfunction "2_2") (pintype "unspecified"))
      (node (ref "R7") (pin "1") (pinfunction "1_1") (pintype "unspecified"))
    )
    (net (code "55") (name "Vin") (class "Default")
      (node (ref "C2") (pin "2") (pinfunction "2_2") (pintype "unspecified"))
      (node (ref "C3") (pin "2") (pinfunction "2_2") (pintype "unspecified"))
      (node (ref "C6") (pin "2") (pinfunction "2_2") (pintype "unspecified"))
      (node (ref "R1") (pin "1") (pinfunction "1_1") (pintype "unspecified"))
      (node (ref "R13") (pin "1") (pinfunction "1_1") (pintype "unspecified"))
      (node (ref "U1") (pin "5") (pinfunction "IN_5") (pintype "unspecified"))
      (node (ref "U2") (pin "5") (pinfunction "VIN_5") (pintype "unspecified"))
      (node (ref "U3") (pin "1") (pinfunction "1_1") (pintype "input"))
    )
    (net (code "56") (name "unconnected-(CN1-Pad7)") (class "Default")
      (node (ref "CN1") (pin "7") (pinfunction "7_7") (pintype "unspecified"))
    )
    (net (code "57") (name "unconnected-(CN1-Pad8)") (class "Default")
      (node (ref "CN1") (pin "8") (pinfunction "8_8") (pintype "unspecified"))
    )
    (net (code "58") (name "unconnected-(CN2-Pad5)") (class "Default")
      (node (ref "CN2") (pin "5") (pinfunction "5_5") (pintype "unspecified"))
    )
    (net (code "59") (name "unconnected-(CN2-Pad6)") (class "Default")
      (node (ref "CN2") (pin "6") (pinfunction "6_6") (pintype "unspecified"))
    )
    (net (code "60") (name "unconnected-(CN3-Pad3)") (class "Default")
      (node (ref "CN3") (pin "3") (pinfunction "3_3") (pintype "unspecified"))
    )
    (net (code "61") (name "unconnected-(CN3-Pad4)") (class "Default")
      (node (ref "CN3") (pin "4") (pinfunction "4_4") (pintype "unspecified"))
    )
    (net (code "62") (name "unconnected-(CN4-Pad1)") (class "Default")
      (node (ref "CN4") (pin "1") (pinfunction "1_1") (pintype "unspecified"))
    )
    (net (code "63") (name "unconnected-(CN4-Pad2)") (class "Default")
      (node (ref "CN4") (pin "2") (pinfunction "2_2") (pintype "unspecified"))
    )
    (net (code "64") (name "unconnected-(CN4-Pad3)") (class "Default")
      (node (ref "CN4") (pin "3") (pinfunction "3_3") (pintype "unspecified"))
    )
    (net (code "65") (name "unconnected-(CN4-Pad4)") (class "Default")
      (node (ref "CN4") (pin "4") (pinfunction "4_4") (pintype "unspecified"))
    )
    (net (code "66") (name "unconnected-(CN4-Pad5)") (class "Default")
      (node (ref "CN4") (pin "5") (pinfunction "5_5") (pintype "unspecified"))
    )
    (net (code "67") (name "unconnected-(CN5-Pad2)") (class "Default")
      (node (ref "CN5") (pin "2") (pinfunction "2_2") (pintype "unspecified"))
    )
    (net (code "68") (name "unconnected-(CN5-Pad4)") (class "Default")
      (node (ref "CN5") (pin "4") (pinfunction "4_4") (pintype "unspecified"))
    )
    (net (code "69") (name "unconnected-(CN5-Pad5)") (class "Default")
      (node (ref "CN5") (pin "5") (pinfunction "5_5") (pintype "unspecified"))
    )
    (net (code "70") (name "unconnected-(CN6-Pad4)") (class "Default")
      (node (ref "CN6") (pin "4") (pinfunction "4_4") (pintype "unspecified"))
    )
    (net (code "71") (name "unconnected-(CN6-Pad5)") (class "Default")
      (node (ref "CN6") (pin "5") (pinfunction "5_5") (pintype "unspecified"))
    )
    (net (code "72") (name "unconnected-(L3-IO4-Pad26)") (class "Default")
      (node (ref "L3") (pin "26") (pinfunction "IO4_26") (pintype "unspecified"))
    )
    (net (code "73") (name "unconnected-(L3-IO5-Pad29)") (class "Default")
      (node (ref "L3") (pin "29") (pinfunction "IO5_29") (pintype "unspecified"))
    )
    (net (code "74") (name "unconnected-(L3-IO12-Pad14)") (class "Default")
      (node (ref "L3") (pin "14") (pinfunction "IO12_14") (pintype "unspecified"))
    )
    (net (code "75") (name "unconnected-(L3-IO13-Pad16)") (class "Default")
      (node (ref "L3") (pin "16") (pinfunction "IO13_16") (pintype "unspecified"))
    )
    (net (code "76") (name "unconnected-(L3-IO14-Pad13)") (class "Default")
      (node (ref "L3") (pin "13") (pinfunction "IO14_13") (pintype "unspecified"))
    )
    (net (code "77") (name "unconnected-(L3-IO15-Pad23)") (class "Default")
      (node (ref "L3") (pin "23") (pinfunction "IO15_23") (pintype "unspecified"))
    )
    (net (code "78") (name "unconnected-(L3-IO26-Pad11)") (class "Default")
      (node (ref "L3") (pin "11") (pinfunction "IO26_11") (pintype "unspecified"))
    )
    (net (code "79") (name "unconnected-(L3-IO27-Pad12)") (class "Default")
      (node (ref "L3") (pin "12") (pinfunction "IO27_12") (pintype "unspecified"))
    )
    (net (code "80") (name "unconnected-(L3-IO32-Pad8)") (class "Default")
      (node (ref "L3") (pin "8") (pinfunction "IO32_8") (pintype "unspecified"))
    )
    (net (code "81") (name "unconnected-(L3-NC-Pad32)") (class "Default")
      (node (ref "L3") (pin "32") (pinfunction "NC_32") (pintype "unspecified"))
    )
    (net (code "82") (name "unconnected-(L3-SCK{slash}CLK-Pad20)") (class "Default")
      (node (ref "L3") (pin "20") (pinfunction "SCK/CLK_20") (pintype "unspecified"))
    )
    (net (code "83") (name "unconnected-(L3-SCS{slash}CMD-Pad19)") (class "Default")
      (node (ref "L3") (pin "19") (pinfunction "SCS/CMD_19") (pintype "unspecified"))
    )
    (net (code "84") (name "unconnected-(L3-SDI{slash}SD1-Pad22)") (class "Default")
      (node (ref "L3") (pin "22") (pinfunction "SDI/SD1_22") (pintype "unspecified"))
    )
    (net (code "85") (name "unconnected-(L3-SDO{slash}SD0-Pad21)") (class "Default")
      (node (ref "L3") (pin "21") (pinfunction "SDO/SD0_21") (pintype "unspecified"))
    )
    (net (code "86") (name "unconnected-(L3-SENSOR_VN-Pad5)") (class "Default")
      (node (ref "L3") (pin "5") (pinfunction "SENSOR_VN_5") (pintype "unspecified"))
    )
    (net (code "87") (name "unconnected-(L3-SENSOR_VP-Pad4)") (class "Default")
      (node (ref "L3") (pin "4") (pinfunction "SENSOR_VP_4") (pintype "unspecified"))
    )
    (net (code "88") (name "unconnected-(L3-SHD{slash}SD2-Pad17)") (class "Default")
      (node (ref "L3") (pin "17") (pinfunction "SHD/SD2_17") (pintype "unspecified"))
    )
    (net (code "89") (name "unconnected-(L3-SWP{slash}SD3-Pad18)") (class "Default")
      (node (ref "L3") (pin "18") (pinfunction "SWP/SD3_18") (pintype "unspecified"))
    )
    (net (code "90") (name "unconnected-(LED1-+-Pad1)") (class "Default")
      (node (ref "LED1") (pin "1") (pinfunction "+_1") (pintype "unspecified"))
    )
    (net (code "91") (name "unconnected-(LED2-+-Pad1)") (class "Default")
      (node (ref "LED2") (pin "1") (pinfunction "+_1") (pintype "unspecified"))
    )
    (net (code "92") (name "unconnected-(LED3---Pad2)") (class "Default")
      (node (ref "LED3") (pin "2") (pinfunction "-_2") (pintype "unspecified"))
    )
    (net (code "93") (name "unconnected-(LED4-+-Pad1)") (class "Default")
      (node (ref "LED4") (pin "1") (pinfunction "+_1") (pintype "unspecified"))
    )
    (net (code "94") (name "unconnected-(LED5-+-Pad1)") (class "Default")
      (node (ref "LED5") (pin "1") (pinfunction "+_1") (pintype "unspecified"))
    )
    (net (code "95") (name "unconnected-(SW1-Pad3)") (class "Default")
      (node (ref "SW1") (pin "3") (pinfunction "3_3") (pintype "unspecified"))
    )
    (net (code "96") (name "unconnected-(SW1-Pad4)") (class "Default")
      (node (ref "SW1") (pin "4") (pinfunction "4_4") (pintype "unspecified"))
    )
    (net (code "97") (name "unconnected-(U2-SW-Pad3)") (class "Default")
      (node (ref "U2") (pin "3") (pinfunction "SW_3") (pintype "unspecified"))
    )
    (net (code "98") (name "unconnected-(U6-CTS#-Pad9)") (class "Default")
      (node (ref "U6") (pin "9") (pinfunction "CTS#_9") (pintype "unspecified"))
    )
    (net (code "99") (name "unconnected-(U6-DCD#-Pad12)") (class "Default")
      (node (ref "U6") (pin "12") (pinfunction "DCD#_12") (pintype "unspecified"))
    )
    (net (code "100") (name "unconnected-(U6-DSR#-Pad10)") (class "Default")
      (node (ref "U6") (pin "10") (pinfunction "DSR#_10") (pintype "unspecified"))
    )
    (net (code "101") (name "unconnected-(U6-NC.-Pad7)") (class "Default")
      (node (ref "U6") (pin "7") (pinfunction "NC._7") (pintype "unspecified"))
    )
    (net (code "102") (name "unconnected-(U6-OUT#-Pad8)") (class "Default")
      (node (ref "U6") (pin "8") (pinfunction "OUT#_8") (pintype "unspecified"))
    )
    (net (code "103") (name "unconnected-(U6-R232-Pad15)") (class "Default")
      (node (ref "U6") (pin "15") (pinfunction "R232_15") (pintype "unspecified"))
    )
    (net (code "104") (name "unconnected-(U6-RI#-Pad11)") (class "Default")
      (node (ref "U6") (pin "11") (pinfunction "RI#_11") (pintype "unspecified"))
    )
    (net (code "105") (name "unconnected-(U7-IN1+-Pad3)") (class "Default")
      (node (ref "U7") (pin "3") (pinfunction "IN1+_3") (pintype "unspecified"))
    )
    (net (code "106") (name "unconnected-(U7-IN2–-Pad6)") (class "Default")
      (node (ref "U7") (pin "6") (pinfunction "IN2–_6") (pintype "unspecified"))
    )
    (net (code "107") (name "unconnected-(U7-OUT1-Pad1)") (class "Default")
      (node (ref "U7") (pin "1") (pinfunction "OUT1_1") (pintype "unspecified"))
    )
    (net (code "108") (name "unconnected-(U11-BAT_STAT-Pad5)") (class "Default")
      (node (ref "U11") (pin "5") (pinfunction "BAT_STAT_5") (pintype "unspecified"))
    )
    (net (code "109") (name "unconnected-(U11-CON_SEL-Pad10)") (class "Default")
      (node (ref "U11") (pin "10") (pinfunction "CON_SEL_10") (pintype "unspecified"))
    )
    (net (code "110") (name "unconnected-(U11-LED-Pad6)") (class "Default")
      (node (ref "U11") (pin "6") (pinfunction "LED_6") (pintype "unspecified"))
    )
    (net (code "111") (name "unconnected-(U11-VSET-Pad3)") (class "Default")
      (node (ref "U11") (pin "3") (pinfunction "VSET_3") (pintype "unspecified"))
    )
    (net (code "112") (name "unconnected-(U12-D-Pad2)") (class "Default")
      (node (ref "U12") (pin "2") (pinfunction "D_2") (pintype "unspecified"))
    )
    (net (code "113") (name "unconnected-(U12-G-Pad1)") (class "Default")
      (node (ref "U12") (pin "1") (pinfunction "G_1") (pintype "unspecified"))
    )
    (net (code "114") (name "unconnected-(U12-S-Pad3)") (class "Default")
      (node (ref "U12") (pin "3") (pinfunction "S_3") (pintype "unspecified"))
    )
  )
)
